# Sheet2.net
KiCad netlist of a schematic drawn in Altium Designer
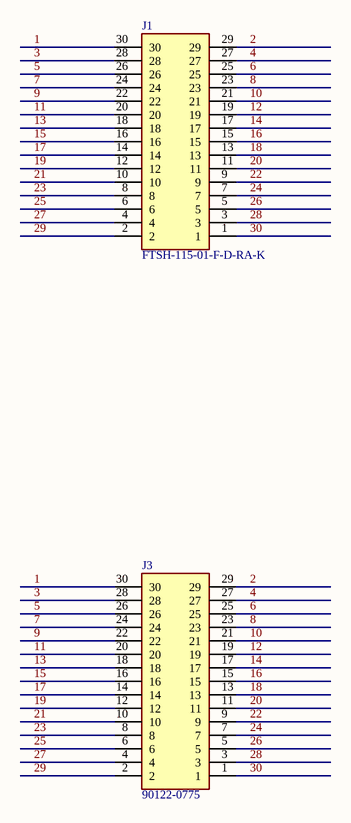
[diagram p0: Sheet2.SchDoc]

(export (version "E")
  (design (tool "Eeschema 10.0.6"))
  (components
    (comp (ref "J1")
      (value "FTSH-115-01-F-D-RA-K")
      (footprint "SamacSys:FTSH-115-XX-YYY-D-RA-K")
      (description "Connector")
      (libsource (lib "*") (part "FTSH-115-01-F-D-RA-K"))
    )
    (comp (ref "J3")
      (value "90122-0775")
      (footprint "SamacSys:HDRRA30W65P254_2X15_3802X250X635P")
      (description "Connector")
      (fields (field (name "MOUSER PART NUMBER") "538-90122-0775"))
      (libsource (lib "*") (part "90122-0775"))
    )
  )
  (nets
    (net (code "1") (name "/1") (class "Default")
      (node (ref "J1") (pin "30") (pinfunction "30_30") (pintype "passive"))
      (node (ref "J3") (pin "30") (pinfunction "30_30") (pintype "passive"))
    )
    (net (code "2") (name "/2") (class "Default")
      (node (ref "J1") (pin "29") (pinfunction "29_29") (pintype "passive"))
      (node (ref "J3") (pin "29") (pinfunction "29_29") (pintype "passive"))
    )
    (net (code "3") (name "/3") (class "Default")
      (node (ref "J1") (pin "28") (pinfunction "28_28") (pintype "passive"))
      (node (ref "J3") (pin "28") (pinfunction "28_28") (pintype "passive"))
    )
    (net (code "4") (name "/4") (class "Default")
      (node (ref "J1") (pin "27") (pinfunction "27_27") (pintype "passive"))
      (node (ref "J3") (pin "27") (pinfunction "27_27") (pintype "passive"))
    )
    (net (code "5") (name "/5") (class "Default")
      (node (ref "J1") (pin "26") (pinfunction "26_26") (pintype "passive"))
      (node (ref "J3") (pin "26") (pinfunction "26_26") (pintype "passive"))
    )
    (net (code "6") (name "/6") (class "Default")
      (node (ref "J1") (pin "25") (pinfunction "25_25") (pintype "passive"))
      (node (ref "J3") (pin "25") (pinfunction "25_25") (pintype "passive"))
    )
    (net (code "7") (name "/7") (class "Default")
      (node (ref "J1") (pin "24") (pinfunction "24_24") (pintype "passive"))
      (node (ref "J3") (pin "24") (pinfunction "24_24") (pintype "passive"))
    )
    (net (code "8") (name "/8") (class "Default")
      (node (ref "J1") (pin "23") (pinfunction "23_23") (pintype "passive"))
      (node (ref "J3") (pin "23") (pinfunction "23_23") (pintype "passive"))
    )
    (net (code "9") (name "/9") (class "Default")
      (node (ref "J1") (pin "22") (pinfunction "22_22") (pintype "passive"))
      (node (ref "J3") (pin "22") (pinfunction "22_22") (pintype "passive"))
    )
    (net (code "10") (name "/10") (class "Default")
      (node (ref "J1") (pin "21") (pinfunction "21_21") (pintype "passive"))
      (node (ref "J3") (pin "21") (pinfunction "21_21") (pintype "passive"))
    )
    (net (code "11") (name "/11") (class "Default")
      (node (ref "J1") (pin "20") (pinfunction "20_20") (pintype "passive"))
      (node (ref "J3") (pin "20") (pinfunction "20_20") (pintype "passive"))
    )
    (net (code "12") (name "/12") (class "Default")
      (node (ref "J1") (pin "19") (pinfunction "19_19") (pintype "passive"))
      (node (ref "J3") (pin "19") (pinfunction "19_19") (pintype "passive"))
    )
    (net (code "13") (name "/13") (class "Default")
      (node (ref "J1") (pin "18") (pinfunction "18_18") (pintype "passive"))
      (node (ref "J3") (pin "18") (pinfunction "18_18") (pintype "passive"))
    )
    (net (code "14") (name "/14") (class "Default")
      (node (ref "J1") (pin "17") (pinfunction "17_17") (pintype "passive"))
      (node (ref "J3") (pin "17") (pinfunction "17_17") (pintype "passive"))
    )
    (net (code "15") (name "/15") (class "Default")
      (node (ref "J1") (pin "16") (pinfunction "16_16") (pintype "passive"))
      (node (ref "J3") (pin "16") (pinfunction "16_16") (pintype "passive"))
    )
    (net (code "16") (name "/16") (class "Default")
      (node (ref "J1") (pin "15") (pinfunction "15_15") (pintype "passive"))
      (node (ref "J3") (pin "15") (pinfunction "15_15") (pintype "passive"))
    )
    (net (code "17") (name "/17") (class "Default")
      (node (ref "J1") (pin "14") (pinfunction "14_14") (pintype "passive"))
      (node (ref "J3") (pin "14") (pinfunction "14_14") (pintype "passive"))
    )
    (net (code "18") (name "/18") (class "Default")
      (node (ref "J1") (pin "13") (pinfunction "13_13") (pintype "passive"))
      (node (ref "J3") (pin "13") (pinfunction "13_13") (pintype "passive"))
    )
    (net (code "19") (name "/19") (class "Default")
      (node (ref "J1") (pin "12") (pinfunction "12_12") (pintype "passive"))
      (node (ref "J3") (pin "12") (pinfunction "12_12") (pintype "passive"))
    )
    (net (code "20") (name "/20") (class "Default")
      (node (ref "J1") (pin "11") (pinfunction "11_11") (pintype "passive"))
      (node (ref "J3") (pin "11") (pinfunction "11_11") (pintype "passive"))
    )
    (net (code "21") (name "/21") (class "Default")
      (node (ref "J1") (pin "10") (pinfunction "10_10") (pintype "passive"))
      (node (ref "J3") (pin "10") (pinfunction "10_10") (pintype "passive"))
    )
    (net (code "22") (name "/22") (class "Default")
      (node (ref "J1") (pin "9") (pinfunction "9_9") (pintype "passive"))
      (node (ref "J3") (pin "9") (pinfunction "9_9") (pintype "passive"))
    )
    (net (code "23") (name "/23") (class "Default")
      (node (ref "J1") (pin "8") (pinfunction "8_8") (pintype "passive"))
      (node (ref "J3") (pin "8") (pinfunction "8_8") (pintype "passive"))
    )
    (net (code "24") (name "/24") (class "Default")
      (node (ref "J1") (pin "7") (pinfunction "7_7") (pintype "passive"))
      (node (ref "J3") (pin "7") (pinfunction "7_7") (pintype "passive"))
    )
    (net (code "25") (name "/25") (class "Default")
      (node (ref "J1") (pin "6") (pinfunction "6_6") (pintype "passive"))
      (node (ref "J3") (pin "6") (pinfunction "6_6") (pintype "passive"))
    )
    (net (code "26") (name "/26") (class "Default")
      (node (ref "J1") (pin "5") (pinfunction "5_5") (pintype "passive"))
      (node (ref "J3") (pin "5") (pinfunction "5_5") (pintype "passive"))
    )
    (net (code "27") (name "/27") (class "Default")
      (node (ref "J1") (pin "4") (pinfunction "4_4") (pintype "passive"))
      (node (ref "J3") (pin "4") (pinfunction "4_4") (pintype "passive"))
    )
    (net (code "28") (name "/28") (class "Default")
      (node (ref "J1") (pin "3") (pinfunction "3_3") (pintype "passive"))
      (node (ref "J3") (pin "3") (pinfunction "3_3") (pintype "passive"))
    )
    (net (code "29") (name "/29") (class "Default")
      (node (ref "J1") (pin "2") (pinfunction "2_2") (pintype "passive"))
      (node (ref "J3") (pin "2") (pinfunction "2_2") (pintype "passive"))
    )
    (net (code "30") (name "/30") (class "Default")
      (node (ref "J1") (pin "1") (pinfunction "1_1") (pintype "passive"))
      (node (ref "J3") (pin "1") (pinfunction "1_1") (pintype "passive"))
    )
  )
)
